# Rear__light_via.net
KiCad netlist of a schematic drawn in EAGLE
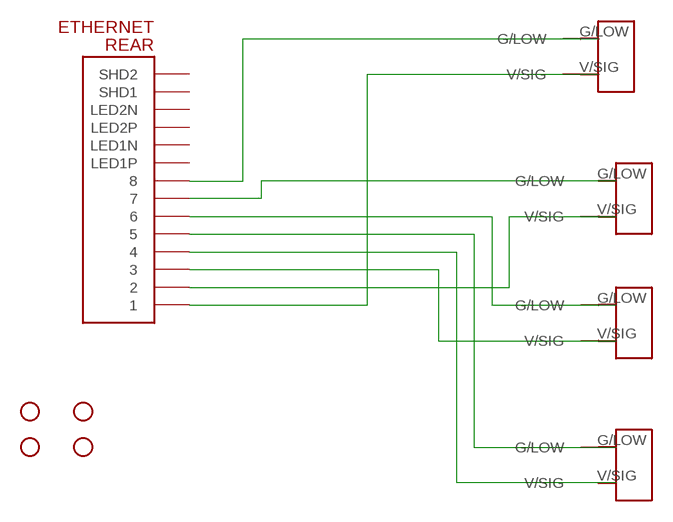
[diagram p0: schematic, sheet 1]

(export (version "E")
  (design (tool "Eeschema 10.0.6"))
  (components
    (comp (ref "H1")
      (value "STAND-OFF")
      (footprint "eagle-import:STAND-OFF")
      (libsource (lib "eagle-import") (part "STAND-OFF"))
    )
    (comp (ref "H2")
      (value "STAND-OFF")
      (footprint "eagle-import:STAND-OFF")
      (libsource (lib "eagle-import") (part "STAND-OFF"))
    )
    (comp (ref "H3")
      (value "STAND-OFF")
      (footprint "eagle-import:STAND-OFF")
      (libsource (lib "eagle-import") (part "STAND-OFF"))
    )
    (comp (ref "H4")
      (value "STAND-OFF")
      (footprint "eagle-import:STAND-OFF")
      (libsource (lib "eagle-import") (part "STAND-OFF"))
    )
    (comp (ref "REAR")
      (value "ETHERNET")
      (footprint "eagle-import:A122645-ND")
      (libsource (lib "eagle-import") (part "ETHERNET"))
    )
    (comp (ref "U$1")
      (value "2_PIN_TECONNECTOR")
      (footprint "eagle-import:2_PIN_CONNECT")
      (libsource (lib "eagle-import") (part "2_PIN_TECONNECTOR"))
    )
    (comp (ref "U$2")
      (value "2_PIN_TECONNECTOR")
      (footprint "eagle-import:2_PIN_CONNECT")
      (libsource (lib "eagle-import") (part "2_PIN_TECONNECTOR"))
    )
    (comp (ref "U$3")
      (value "2_PIN_TECONNECTOR")
      (footprint "eagle-import:2_PIN_CONNECT")
      (libsource (lib "eagle-import") (part "2_PIN_TECONNECTOR"))
    )
    (comp (ref "U$4")
      (value "2_PIN_TECONNECTOR")
      (footprint "eagle-import:2_PIN_CONNECT")
      (libsource (lib "eagle-import") (part "2_PIN_TECONNECTOR"))
    )
  )
  (nets
    (net (code "1") (name "Net-(REAR-1)") (class "Default")
      (node (ref "REAR") (pin "P$1") (pinfunction "1_P$1") (pintype "bidirectional"))
      (node (ref "U$1") (pin "V/SIG") (pinfunction "V/SIG_V/SIG") (pintype "bidirectional"))
    )
    (net (code "2") (name "Net-(REAR-2)") (class "Default")
      (node (ref "REAR") (pin "P$2") (pinfunction "2_P$2") (pintype "bidirectional"))
      (node (ref "U$2") (pin "V/SIG") (pinfunction "V/SIG_V/SIG") (pintype "bidirectional"))
    )
    (net (code "3") (name "Net-(REAR-3)") (class "Default")
      (node (ref "REAR") (pin "P$3") (pinfunction "3_P$3") (pintype "bidirectional"))
      (node (ref "U$3") (pin "V/SIG") (pinfunction "V/SIG_V/SIG") (pintype "bidirectional"))
    )
    (net (code "4") (name "Net-(REAR-4)") (class "Default")
      (node (ref "REAR") (pin "P$4") (pinfunction "4_P$4") (pintype "bidirectional"))
      (node (ref "U$4") (pin "V/SIG") (pinfunction "V/SIG_V/SIG") (pintype "bidirectional"))
    )
    (net (code "5") (name "Net-(REAR-5)") (class "Default")
      (node (ref "REAR") (pin "P$5") (pinfunction "5_P$5") (pintype "bidirectional"))
      (node (ref "U$4") (pin "G/LOW") (pinfunction "G/LOW_G/LOW") (pintype "bidirectional"))
    )
    (net (code "6") (name "Net-(REAR-6)") (class "Default")
      (node (ref "REAR") (pin "P$6") (pinfunction "6_P$6") (pintype "bidirectional"))
      (node (ref "U$3") (pin "G/LOW") (pinfunction "G/LOW_G/LOW") (pintype "bidirectional"))
    )
    (net (code "7") (name "Net-(REAR-7)") (class "Default")
      (node (ref "REAR") (pin "P$7") (pinfunction "7_P$7") (pintype "bidirectional"))
      (node (ref "U$2") (pin "G/LOW") (pinfunction "G/LOW_G/LOW") (pintype "bidirectional"))
    )
    (net (code "8") (name "Net-(REAR-8)") (class "Default")
      (node (ref "REAR") (pin "P$8") (pinfunction "8_P$8") (pintype "bidirectional"))
      (node (ref "U$1") (pin "G/LOW") (pinfunction "G/LOW_G/LOW") (pintype "bidirectional"))
    )
    (net (code "9") (name "unconnected-(REAR-LED1N-PadP$9)") (class "Default")
      (node (ref "REAR") (pin "P$9") (pinfunction "LED1N_P$9") (pintype "bidirectional"))
    )
    (net (code "10") (name "unconnected-(REAR-LED1P-PadP$10)") (class "Default")
      (node (ref "REAR") (pin "P$10") (pinfunction "LED1P_P$10") (pintype "bidirectional"))
    )
    (net (code "11") (name "unconnected-(REAR-LED2N-PadP$11)") (class "Default")
      (node (ref "REAR") (pin "P$11") (pinfunction "LED2N_P$11") (pintype "bidirectional"))
    )
    (net (code "12") (name "unconnected-(REAR-LED2P-PadP$12)") (class "Default")
      (node (ref "REAR") (pin "P$12") (pinfunction "LED2P_P$12") (pintype "bidirectional"))
    )
    (net (code "13") (name "unconnected-(REAR-SHD1-PadP$13)") (class "Default")
      (node (ref "REAR") (pin "P$13") (pinfunction "SHD1_P$13") (pintype "bidirectional"))
    )
    (net (code "14") (name "unconnected-(REAR-SHD2-PadP$14)") (class "Default")
      (node (ref "REAR") (pin "P$14") (pinfunction "SHD2_P$14") (pintype "bidirectional"))
    )
  )
)
